# seitanclock.net
KiCad netlist of a schematic drawn in EAGLE
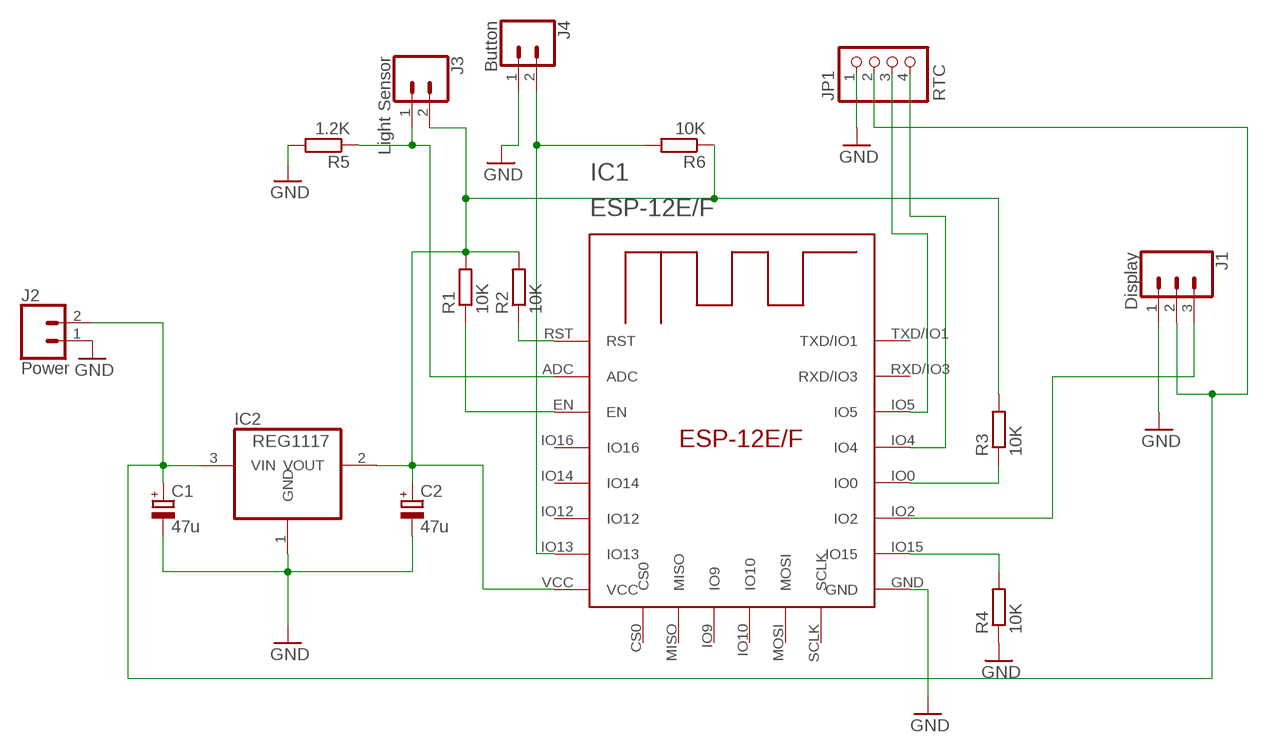
[diagram p0: schematic, sheet 1]

(export (version "E")
  (design (tool "Eeschema 10.0.6"))
  (components
    (comp (ref "C1")
      (value "47u")
      (footprint "eagle-import:153CLV-0605")
      (libsource (lib "eagle-import") (part "CPOL-EU153CLV-0605"))
    )
    (comp (ref "C2")
      (value "47u")
      (footprint "eagle-import:153CLV-0605")
      (libsource (lib "eagle-import") (part "CPOL-EU153CLV-0605"))
    )
    (comp (ref "IC1")
      (value "ESP-12E/F")
      (footprint "eagle-import:ESP-12E")
      (libsource (lib "eagle-import") (part "ESP-12E/F"))
    )
    (comp (ref "IC2")
      (value "REG1117")
      (footprint "eagle-import:SOT223")
      (libsource (lib "eagle-import") (part "REG1117"))
    )
    (comp (ref "J1")
      (value "Display")
      (footprint "eagle-import:MOLEX-1X3")
      (libsource (lib "eagle-import") (part "CONN_03POLAR"))
    )
    (comp (ref "J2")
      (value "Power")
      (footprint "eagle-import:MOLEX-1X2")
      (libsource (lib "eagle-import") (part "CONN_02POLAR"))
    )
    (comp (ref "J3")
      (value "Light Sensor")
      (footprint "eagle-import:MOLEX-1X2")
      (libsource (lib "eagle-import") (part "CONN_02POLAR"))
    )
    (comp (ref "J4")
      (value "Button")
      (footprint "eagle-import:MOLEX-1X2")
      (libsource (lib "eagle-import") (part "CONN_02POLAR"))
    )
    (comp (ref "JP1")
      (value "RTC")
      (footprint "eagle-import:1X04")
      (libsource (lib "eagle-import") (part "PINHD-1X4"))
    )
    (comp (ref "R1")
      (value "10K")
      (footprint "eagle-import:R1206")
      (libsource (lib "eagle-import") (part "R-EU_R1206"))
    )
    (comp (ref "R2")
      (value "10K")
      (footprint "eagle-import:R1206")
      (libsource (lib "eagle-import") (part "R-EU_R1206"))
    )
    (comp (ref "R3")
      (value "10K")
      (footprint "eagle-import:R1206")
      (libsource (lib "eagle-import") (part "R-EU_R1206"))
    )
    (comp (ref "R4")
      (value "10K")
      (footprint "eagle-import:R1206")
      (libsource (lib "eagle-import") (part "R-EU_R1206"))
    )
    (comp (ref "R5")
      (value "1.2K")
      (footprint "eagle-import:R1206")
      (libsource (lib "eagle-import") (part "R-EU_R1206"))
    )
    (comp (ref "R6")
      (value "10K")
      (footprint "eagle-import:R1206")
      (libsource (lib "eagle-import") (part "R-EU_R1206"))
    )
  )
  (nets
    (net (code "1") (name "GND") (class "Default")
      (node (ref "C1") (pin "-") (pinfunction "-_-") (pintype "passive"))
      (node (ref "C2") (pin "-") (pinfunction "-_-") (pintype "passive"))
      (node (ref "IC1") (pin "GND") (pinfunction "GND_GND") (pintype "power_in"))
      (node (ref "IC2") (pin "1") (pinfunction "GND_1") (pintype "power_in"))
      (node (ref "J1") (pin "1") (pinfunction "1_1") (pintype "passive"))
      (node (ref "J2") (pin "1") (pinfunction "1_1") (pintype "passive"))
      (node (ref "J4") (pin "1") (pinfunction "1_1") (pintype "passive"))
      (node (ref "JP1") (pin "1") (pinfunction "1_1") (pintype "passive"))
      (node (ref "R4") (pin "1") (pinfunction "1_1") (pintype "passive"))
      (node (ref "R5") (pin "2") (pinfunction "2_2") (pintype "passive"))
    )
    (net (code "2") (name "Net-(IC1-PadADC)") (class "Default")
      (node (ref "IC1") (pin "ADC") (pinfunction "ADC_ADC") (pintype "bidirectional"))
      (node (ref "J3") (pin "1") (pinfunction "1_1") (pintype "passive"))
      (node (ref "R5") (pin "1") (pinfunction "1_1") (pintype "passive"))
    )
    (net (code "3") (name "Net-(IC1-PadEN)") (class "Default")
      (node (ref "IC1") (pin "EN") (pinfunction "EN_EN") (pintype "bidirectional"))
      (node (ref "R1") (pin "1") (pinfunction "1_1") (pintype "passive"))
    )
    (net (code "4") (name "Net-(IC1-PadIO0)") (class "Default")
      (node (ref "IC1") (pin "IO0") (pinfunction "IO0_IO0") (pintype "bidirectional"))
      (node (ref "R3") (pin "1") (pinfunction "1_1") (pintype "passive"))
    )
    (net (code "5") (name "Net-(IC1-PadIO2)") (class "Default")
      (node (ref "IC1") (pin "IO2") (pinfunction "IO2_IO2") (pintype "bidirectional"))
      (node (ref "J1") (pin "3") (pinfunction "3_3") (pintype "passive"))
    )
    (net (code "6") (name "Net-(IC1-PadIO4)") (class "Default")
      (node (ref "IC1") (pin "IO4") (pinfunction "IO4_IO4") (pintype "bidirectional"))
      (node (ref "JP1") (pin "4") (pinfunction "4_4") (pintype "passive"))
    )
    (net (code "7") (name "Net-(IC1-PadIO5)") (class "Default")
      (node (ref "IC1") (pin "IO5") (pinfunction "IO5_IO5") (pintype "bidirectional"))
      (node (ref "JP1") (pin "3") (pinfunction "3_3") (pintype "passive"))
    )
    (net (code "8") (name "Net-(IC1-PadIO13)") (class "Default")
      (node (ref "IC1") (pin "IO13") (pinfunction "IO13_IO13") (pintype "bidirectional"))
      (node (ref "J4") (pin "2") (pinfunction "2_2") (pintype "passive"))
      (node (ref "R6") (pin "2") (pinfunction "2_2") (pintype "passive"))
    )
    (net (code "9") (name "Net-(IC1-PadIO15)") (class "Default")
      (node (ref "IC1") (pin "IO15") (pinfunction "IO15_IO15") (pintype "bidirectional"))
      (node (ref "R4") (pin "2") (pinfunction "2_2") (pintype "passive"))
    )
    (net (code "10") (name "Net-(IC1-PadRST)") (class "Default")
      (node (ref "IC1") (pin "RST") (pinfunction "RST_RST") (pintype "input"))
      (node (ref "R2") (pin "1") (pinfunction "1_1") (pintype "passive"))
    )
    (net (code "11") (name "Net-(IC2-VIN)") (class "Default")
      (node (ref "C1") (pin "+") (pinfunction "+_+") (pintype "passive"))
      (node (ref "IC2") (pin "3") (pinfunction "VIN_3") (pintype "input"))
      (node (ref "J1") (pin "2") (pinfunction "2_2") (pintype "passive"))
      (node (ref "J2") (pin "2") (pinfunction "2_2") (pintype "passive"))
      (node (ref "JP1") (pin "2") (pinfunction "2_2") (pintype "passive"))
    )
    (net (code "12") (name "Net-(IC2-VOUT)") (class "Default")
      (node (ref "C2") (pin "+") (pinfunction "+_+") (pintype "passive"))
      (node (ref "IC1") (pin "VCC") (pinfunction "VCC_VCC") (pintype "power_in"))
      (node (ref "IC2") (pin "2") (pinfunction "VOUT_2") (pintype "output"))
      (node (ref "J3") (pin "2") (pinfunction "2_2") (pintype "passive"))
      (node (ref "R1") (pin "2") (pinfunction "2_2") (pintype "passive"))
      (node (ref "R2") (pin "2") (pinfunction "2_2") (pintype "passive"))
      (node (ref "R3") (pin "2") (pinfunction "2_2") (pintype "passive"))
      (node (ref "R6") (pin "1") (pinfunction "1_1") (pintype "passive"))
    )
    (net (code "13") (name "unconnected-(IC1-PadCS0)") (class "Default")
      (node (ref "IC1") (pin "CS0") (pinfunction "CS0_CS0") (pintype "bidirectional"))
    )
    (net (code "14") (name "unconnected-(IC1-PadIO9)") (class "Default")
      (node (ref "IC1") (pin "IO9") (pinfunction "IO9_IO9") (pintype "bidirectional"))
    )
    (net (code "15") (name "unconnected-(IC1-PadIO10)") (class "Default")
      (node (ref "IC1") (pin "IO10") (pinfunction "IO10_IO10") (pintype "bidirectional"))
    )
    (net (code "16") (name "unconnected-(IC1-PadIO12)") (class "Default")
      (node (ref "IC1") (pin "IO12") (pinfunction "IO12_IO12") (pintype "bidirectional"))
    )
    (net (code "17") (name "unconnected-(IC1-PadIO14)") (class "Default")
      (node (ref "IC1") (pin "IO14") (pinfunction "IO14_IO14") (pintype "bidirectional"))
    )
    (net (code "18") (name "unconnected-(IC1-PadIO16)") (class "Default")
      (node (ref "IC1") (pin "IO16") (pinfunction "IO16_IO16") (pintype "bidirectional"))
    )
    (net (code "19") (name "unconnected-(IC1-PadMISO)") (class "Default")
      (node (ref "IC1") (pin "MISO") (pinfunction "MISO_MISO") (pintype "bidirectional"))
    )
    (net (code "20") (name "unconnected-(IC1-PadMOSI)") (class "Default")
      (node (ref "IC1") (pin "MOSI") (pinfunction "MOSI_MOSI") (pintype "bidirectional"))
    )
    (net (code "21") (name "unconnected-(IC1-PadRXD{slash}IO3)") (class "Default")
      (node (ref "IC1") (pin "RXD/IO3") (pinfunction "RXD/IO3_RXD/IO3") (pintype "bidirectional"))
    )
    (net (code "22") (name "unconnected-(IC1-PadSCLK)") (class "Default")
      (node (ref "IC1") (pin "SCLK") (pinfunction "SCLK_SCLK") (pintype "bidirectional"))
    )
    (net (code "23") (name "unconnected-(IC1-PadTXD{slash}IO1)") (class "Default")
      (node (ref "IC1") (pin "TXD/IO1") (pinfunction "TXD/IO1_TXD/IO1") (pintype "bidirectional"))
    )
  )
)
